# P5b_Filter2A.net
KiCad netlist of a schematic drawn in Altium Designer
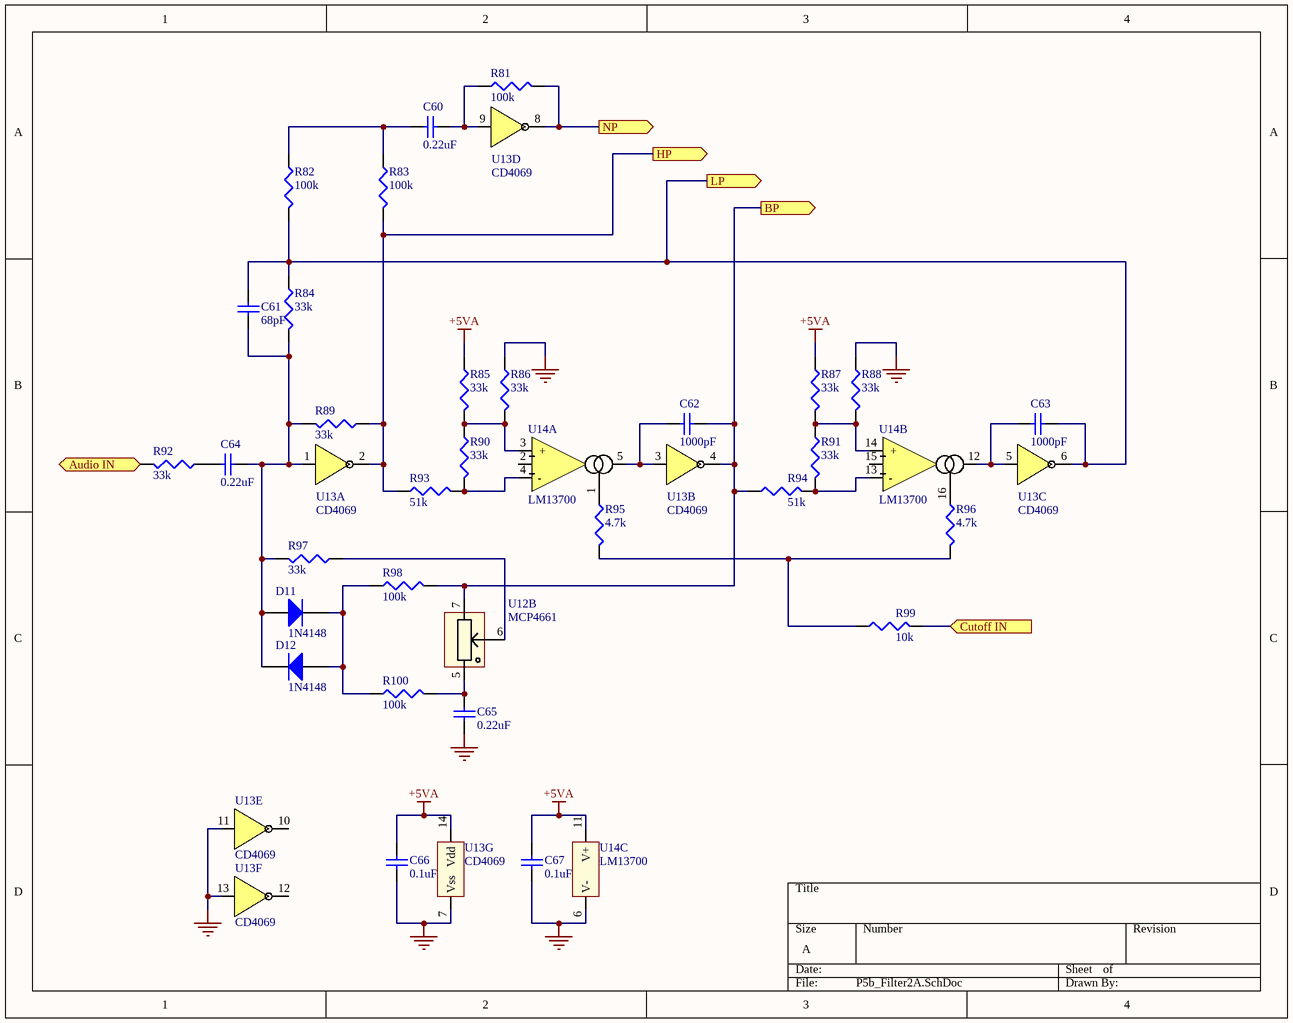
[diagram p0: P5b_Filter2A.SchDoc]

(export (version "E")
  (design (tool "Eeschema 10.0.6"))
  (components
    (comp (ref "C60")
      (value "0.22uF")
      (footprint "CAP 0603 (1608 metric)")
      (description "Capacitor (Semiconductor SIM Model)")
      (libsource (lib "Miscellaneous Devices") (part "Cap Semi"))
    )
    (comp (ref "C61")
      (value "68pF")
      (footprint "CAP 0603 (1608 metric)")
      (description "Capacitor (Semiconductor SIM Model)")
      (libsource (lib "Miscellaneous Devices") (part "Cap Semi"))
    )
    (comp (ref "C62")
      (value "1000pF")
      (footprint "CAP 0603 (1608 metric)")
      (description "Capacitor (Semiconductor SIM Model)")
      (libsource (lib "Miscellaneous Devices") (part "Cap Semi"))
    )
    (comp (ref "C63")
      (value "1000pF")
      (footprint "CAP 0603 (1608 metric)")
      (description "Capacitor (Semiconductor SIM Model)")
      (libsource (lib "Miscellaneous Devices") (part "Cap Semi"))
    )
    (comp (ref "C64")
      (value "0.22uF")
      (footprint "CAP 0603 (1608 metric)")
      (description "Capacitor (Semiconductor SIM Model)")
      (libsource (lib "Miscellaneous Devices") (part "Cap Semi"))
    )
    (comp (ref "C65")
      (value "0.22uF")
      (footprint "CAP 0603 (1608 metric)")
      (description "Capacitor (Semiconductor SIM Model)")
      (libsource (lib "Miscellaneous Devices") (part "Cap Semi"))
    )
    (comp (ref "C66")
      (value "0.1uF")
      (footprint "CAP 0603 (1608 metric)")
      (description "Capacitor (Semiconductor SIM Model)")
      (libsource (lib "Miscellaneous Devices") (part "Cap Semi"))
    )
    (comp (ref "C67")
      (value "0.1uF")
      (footprint "CAP 0603 (1608 metric)")
      (description "Capacitor (Semiconductor SIM Model)")
      (libsource (lib "Miscellaneous Devices") (part "Cap Semi"))
    )
    (comp (ref "D11")
      (value "1N4148")
      (description "High Conductance Fast Diode")
      (libsource (lib "Miscellaneous Devices") (part "Diode 1N4148"))
    )
    (comp (ref "D12")
      (value "1N4148")
      (description "High Conductance Fast Diode")
      (libsource (lib "Miscellaneous Devices") (part "Diode 1N4148"))
    )
    (comp (ref "R81")
      (value "100k")
      (footprint "RES 0603 (1608 metric)")
      (description "Resistor")
      (libsource (lib "Miscellaneous Devices") (part "Res3"))
    )
    (comp (ref "R82")
      (value "100k")
      (footprint "RES 0603 (1608 metric)")
      (description "Resistor")
      (libsource (lib "Miscellaneous Devices") (part "Res3"))
    )
    (comp (ref "R83")
      (value "100k")
      (footprint "RES 0603 (1608 metric)")
      (description "Resistor")
      (libsource (lib "Miscellaneous Devices") (part "Res3"))
    )
    (comp (ref "R84")
      (value "33k")
      (footprint "RES 0603 (1608 metric)")
      (description "Resistor")
      (libsource (lib "Miscellaneous Devices") (part "Res3"))
    )
    (comp (ref "R85")
      (value "33k")
      (footprint "RES 0603 (1608 metric)")
      (description "Resistor")
      (libsource (lib "Miscellaneous Devices") (part "Res3"))
    )
    (comp (ref "R86")
      (value "33k")
      (footprint "RES 0603 (1608 metric)")
      (description "Resistor")
      (libsource (lib "Miscellaneous Devices") (part "Res3"))
    )
    (comp (ref "R87")
      (value "33k")
      (footprint "RES 0603 (1608 metric)")
      (description "Resistor")
      (libsource (lib "Miscellaneous Devices") (part "Res3"))
    )
    (comp (ref "R88")
      (value "33k")
      (footprint "RES 0603 (1608 metric)")
      (description "Resistor")
      (libsource (lib "Miscellaneous Devices") (part "Res3"))
    )
    (comp (ref "R89")
      (value "33k")
      (footprint "RES 0603 (1608 metric)")
      (description "Resistor")
      (libsource (lib "Miscellaneous Devices") (part "Res3"))
    )
    (comp (ref "R90")
      (value "33k")
      (footprint "RES 0603 (1608 metric)")
      (description "Resistor")
      (libsource (lib "Miscellaneous Devices") (part "Res3"))
    )
    (comp (ref "R91")
      (value "33k")
      (footprint "RES 0603 (1608 metric)")
      (description "Resistor")
      (libsource (lib "Miscellaneous Devices") (part "Res3"))
    )
    (comp (ref "R92")
      (value "33k")
      (footprint "RES 0603 (1608 metric)")
      (description "Resistor")
      (libsource (lib "Miscellaneous Devices") (part "Res3"))
    )
    (comp (ref "R93")
      (value "51k")
      (footprint "RES 0603 (1608 metric)")
      (description "Resistor")
      (libsource (lib "Miscellaneous Devices") (part "Res3"))
    )
    (comp (ref "R94")
      (value "51k")
      (footprint "RES 0603 (1608 metric)")
      (description "Resistor")
      (libsource (lib "Miscellaneous Devices") (part "Res3"))
    )
    (comp (ref "R95")
      (value "4.7k")
      (footprint "RES 0603 (1608 metric)")
      (description "Resistor")
      (libsource (lib "Miscellaneous Devices") (part "Res3"))
    )
    (comp (ref "R96")
      (value "4.7k")
      (footprint "RES 0603 (1608 metric)")
      (description "Resistor")
      (libsource (lib "Miscellaneous Devices") (part "Res3"))
    )
    (comp (ref "R97")
      (value "33k")
      (footprint "RES 0603 (1608 metric)")
      (description "Resistor")
      (libsource (lib "Miscellaneous Devices") (part "Res3"))
    )
    (comp (ref "R98")
      (value "100k")
      (footprint "RES 0603 (1608 metric)")
      (description "Resistor")
      (libsource (lib "Miscellaneous Devices") (part "Res3"))
    )
    (comp (ref "R99")
      (value "10k")
      (footprint "RES 0603 (1608 metric)")
      (description "Resistor")
      (libsource (lib "Miscellaneous Devices") (part "Res3"))
    )
    (comp (ref "R100")
      (value "100k")
      (footprint "RES 0603 (1608 metric)")
      (description "Resistor")
      (libsource (lib "Miscellaneous Devices") (part "Res3"))
    )
    (comp (ref "U12")
      (value "MCP4661")
      (description "Dual DigiPot non volatile I2C")
      (libsource (lib "FilterPoC") (part "MCP4661"))
    )
    (comp (ref "U13")
      (value "CD4069")
      (description "Hex Inverter")
      (libsource (lib "FilterPoC") (part "CD4069"))
    )
    (comp (ref "U14")
      (value "LM13700")
      (description "Dual Transconductance OpAmp")
      (libsource (lib "") (part "LM13700M_1"))
    )
  )
  (nets
    (net (code "1") (name "+5VA") (class "Default")
      (node (ref "C66") (pin "1") (pinfunction "1_1") (pintype "passive"))
      (node (ref "C67") (pin "1") (pinfunction "1_1") (pintype "passive"))
      (node (ref "R85") (pin "1") (pinfunction "1_1") (pintype "passive"))
      (node (ref "R87") (pin "1") (pinfunction "1_1") (pintype "passive"))
      (node (ref "U13") (pin "14") (pinfunction "Vdd_14") (pintype "power_in"))
      (node (ref "U14") (pin "11") (pinfunction "V+_11") (pintype "power_in"))
    )
    (net (code "2") (name "/Audio IN") (class "Default")
      (node (ref "R92") (pin "2") (pinfunction "2_2") (pintype "passive"))
    )
    (net (code "3") (name "/BP") (class "Default")
      (node (ref "C62") (pin "2") (pinfunction "2_2") (pintype "passive"))
      (node (ref "R94") (pin "1") (pinfunction "1_1") (pintype "passive"))
      (node (ref "R98") (pin "2") (pinfunction "2_2") (pintype "passive"))
      (node (ref "U12") (pin "7") (pinfunction "P1A_7") (pintype "passive"))
      (node (ref "U13") (pin "4") (pinfunction "~{B}_4") (pintype "passive"))
    )
    (net (code "4") (name "/Cutoff IN") (class "Default")
      (node (ref "R99") (pin "2") (pinfunction "2_2") (pintype "passive"))
    )
    (net (code "5") (name "/HP") (class "Default")
      (node (ref "R83") (pin "2") (pinfunction "2_2") (pintype "passive"))
      (node (ref "R89") (pin "1") (pinfunction "1_1") (pintype "passive"))
      (node (ref "R93") (pin "1") (pinfunction "1_1") (pintype "passive"))
      (node (ref "U13") (pin "2") (pinfunction "~{A}_2") (pintype "passive"))
    )
    (net (code "6") (name "/LP") (class "Default")
      (node (ref "C61") (pin "2") (pinfunction "2_2") (pintype "passive"))
      (node (ref "C63") (pin "2") (pinfunction "2_2") (pintype "passive"))
      (node (ref "R82") (pin "2") (pinfunction "2_2") (pintype "passive"))
      (node (ref "R84") (pin "1") (pinfunction "1_1") (pintype "passive"))
      (node (ref "U13") (pin "6") (pinfunction "~{C}_6") (pintype "passive"))
    )
    (net (code "7") (name "/NP") (class "Default")
      (node (ref "R81") (pin "2") (pinfunction "2_2") (pintype "passive"))
      (node (ref "U13") (pin "8") (pinfunction "~{D}_8") (pintype "passive"))
    )
    (net (code "8") (name "GND") (class "Default")
      (node (ref "C65") (pin "2") (pinfunction "2_2") (pintype "passive"))
      (node (ref "C66") (pin "2") (pinfunction "2_2") (pintype "passive"))
      (node (ref "C67") (pin "2") (pinfunction "2_2") (pintype "passive"))
      (node (ref "R86") (pin "1") (pinfunction "1_1") (pintype "passive"))
      (node (ref "R88") (pin "1") (pinfunction "1_1") (pintype "passive"))
      (node (ref "U13") (pin "11") (pinfunction "E_11") (pintype "passive"))
      (node (ref "U13") (pin "13") (pinfunction "F_13") (pintype "passive"))
      (node (ref "U13") (pin "7") (pinfunction "Vss_7") (pintype "power_in"))
      (node (ref "U14") (pin "6") (pinfunction "V-_6") (pintype "power_in"))
    )
    (net (code "9") (name "Net-(C60-Pad1)") (class "Default")
      (node (ref "C60") (pin "1") (pinfunction "1_1") (pintype "passive"))
      (node (ref "R82") (pin "1") (pinfunction "1_1") (pintype "passive"))
      (node (ref "R83") (pin "1") (pinfunction "1_1") (pintype "passive"))
    )
    (net (code "10") (name "Net-(C64-Pad1)") (class "Default")
      (node (ref "C64") (pin "1") (pinfunction "1_1") (pintype "passive"))
      (node (ref "R92") (pin "1") (pinfunction "1_1") (pintype "passive"))
    )
    (net (code "11") (name "Net-(D11-A)") (class "Default")
      (node (ref "C61") (pin "1") (pinfunction "1_1") (pintype "passive"))
      (node (ref "C64") (pin "2") (pinfunction "2_2") (pintype "passive"))
      (node (ref "D11") (pin "1") (pinfunction "A_1") (pintype "passive"))
      (node (ref "D12") (pin "2") (pinfunction "K_2") (pintype "passive"))
      (node (ref "R84") (pin "2") (pinfunction "2_2") (pintype "passive"))
      (node (ref "R89") (pin "2") (pinfunction "2_2") (pintype "passive"))
      (node (ref "R97") (pin "2") (pinfunction "2_2") (pintype "passive"))
      (node (ref "U13") (pin "1") (pinfunction "A_1") (pintype "passive"))
    )
    (net (code "12") (name "Net-(D11-K)") (class "Default")
      (node (ref "D11") (pin "2") (pinfunction "K_2") (pintype "passive"))
      (node (ref "D12") (pin "1") (pinfunction "A_1") (pintype "passive"))
      (node (ref "R100") (pin "1") (pinfunction "1_1") (pintype "passive"))
      (node (ref "R98") (pin "1") (pinfunction "1_1") (pintype "passive"))
    )
    (net (code "13") (name "Net-(R95-Pad2)") (class "Default")
      (node (ref "R95") (pin "2") (pinfunction "2_2") (pintype "passive"))
      (node (ref "R96") (pin "2") (pinfunction "2_2") (pintype "passive"))
      (node (ref "R99") (pin "1") (pinfunction "1_1") (pintype "passive"))
    )
    (net (code "14") (name "Net-(U12B-P1B)") (class "Default")
      (node (ref "C65") (pin "1") (pinfunction "1_1") (pintype "passive"))
      (node (ref "R100") (pin "2") (pinfunction "2_2") (pintype "passive"))
      (node (ref "U12") (pin "5") (pinfunction "P1B_5") (pintype "passive"))
    )
    (net (code "15") (name "Net-(U12B-P1W)") (class "Default")
      (node (ref "R97") (pin "1") (pinfunction "1_1") (pintype "passive"))
      (node (ref "U12") (pin "6") (pinfunction "P1W_6") (pintype "passive"))
    )
    (net (code "16") (name "Net-(U13B-B)") (class "Default")
      (node (ref "C62") (pin "1") (pinfunction "1_1") (pintype "passive"))
      (node (ref "U13") (pin "3") (pinfunction "B_3") (pintype "passive"))
      (node (ref "U14") (pin "5") (pinfunction "OUT_5") (pintype "passive"))
    )
    (net (code "17") (name "Net-(U13C-C)") (class "Default")
      (node (ref "C63") (pin "1") (pinfunction "1_1") (pintype "passive"))
      (node (ref "U13") (pin "5") (pinfunction "C_5") (pintype "passive"))
      (node (ref "U14") (pin "12") (pinfunction "OUT_12") (pintype "passive"))
    )
    (net (code "18") (name "Net-(U13D-D)") (class "Default")
      (node (ref "C60") (pin "2") (pinfunction "2_2") (pintype "passive"))
      (node (ref "R81") (pin "1") (pinfunction "1_1") (pintype "passive"))
      (node (ref "U13") (pin "9") (pinfunction "D_9") (pintype "passive"))
    )
    (net (code "19") (name "Net-(U14A-+)") (class "Default")
      (node (ref "R85") (pin "2") (pinfunction "2_2") (pintype "passive"))
      (node (ref "R86") (pin "2") (pinfunction "2_2") (pintype "passive"))
      (node (ref "R90") (pin "1") (pinfunction "1_1") (pintype "passive"))
      (node (ref "U14") (pin "3") (pinfunction "+_3") (pintype "passive"))
    )
    (net (code "20") (name "Net-(U14A--)") (class "Default")
      (node (ref "R90") (pin "2") (pinfunction "2_2") (pintype "passive"))
      (node (ref "R93") (pin "2") (pinfunction "2_2") (pintype "passive"))
      (node (ref "U14") (pin "4") (pinfunction "-_4") (pintype "passive"))
    )
    (net (code "21") (name "Net-(U14A-BIAS)") (class "Default")
      (node (ref "R95") (pin "1") (pinfunction "1_1") (pintype "passive"))
      (node (ref "U14") (pin "1") (pinfunction "BIAS_1") (pintype "passive"))
    )
    (net (code "22") (name "Net-(U14B-+)") (class "Default")
      (node (ref "R87") (pin "2") (pinfunction "2_2") (pintype "passive"))
      (node (ref "R88") (pin "2") (pinfunction "2_2") (pintype "passive"))
      (node (ref "R91") (pin "1") (pinfunction "1_1") (pintype "passive"))
      (node (ref "U14") (pin "14") (pinfunction "+_14") (pintype "passive"))
    )
    (net (code "23") (name "Net-(U14B--)") (class "Default")
      (node (ref "R91") (pin "2") (pinfunction "2_2") (pintype "passive"))
      (node (ref "R94") (pin "2") (pinfunction "2_2") (pintype "passive"))
      (node (ref "U14") (pin "13") (pinfunction "-_13") (pintype "passive"))
    )
    (net (code "24") (name "Net-(U14B-BIAS)") (class "Default")
      (node (ref "R96") (pin "1") (pinfunction "1_1") (pintype "passive"))
      (node (ref "U14") (pin "16") (pinfunction "BIAS_16") (pintype "passive"))
    )
    (net (code "25") (name "unconnected-(U13E-~{E}-Pad10)") (class "Default")
      (node (ref "U13") (pin "10") (pinfunction "~{E}_10") (pintype "passive"))
    )
    (net (code "26") (name "unconnected-(U13F-~{F}-Pad12)") (class "Default")
      (node (ref "U13") (pin "12") (pinfunction "~{F}_12") (pintype "passive"))
    )
    (net (code "27") (name "unconnected-(U14A-Diode_BIAS-Pad2)") (class "Default")
      (node (ref "U14") (pin "2") (pinfunction "Diode_BIAS_2") (pintype "passive"))
    )
    (net (code "28") (name "unconnected-(U14B-Diode_BIAS-Pad15)") (class "Default")
      (node (ref "U14") (pin "15") (pinfunction "Diode_BIAS_15") (pintype "passive"))
    )
  )
)
